# Mezz_connector.net
KiCad netlist of a schematic drawn in Altium Designer
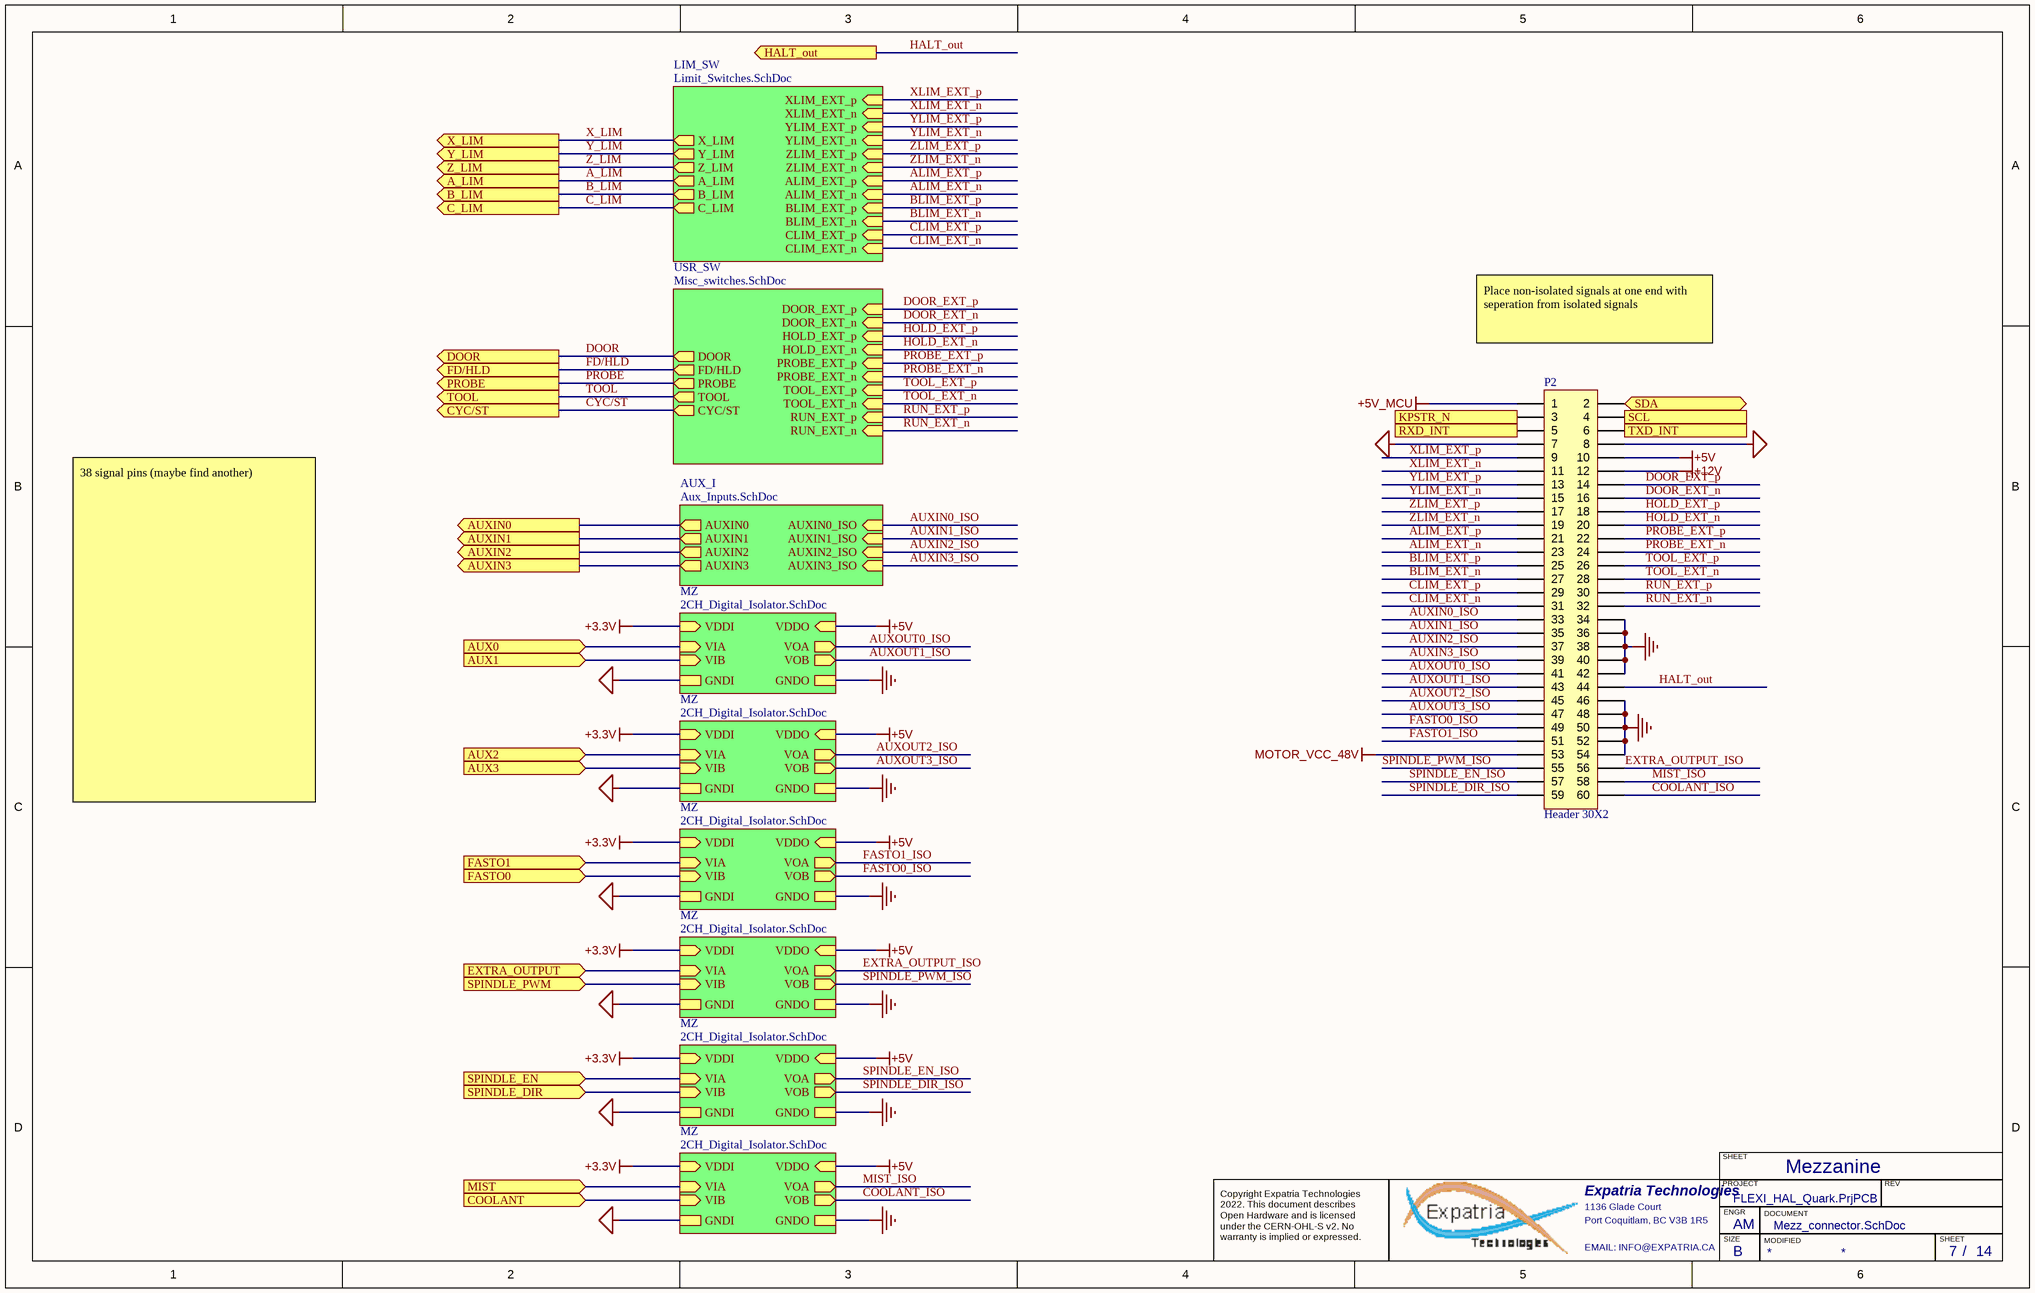
[diagram p0: Mezz_connector.SchDoc]

(export (version "E")
  (design (tool "Eeschema 10.0.6"))
  (components
    (comp (ref "P2")
      (value "Header 30X2")
      (footprint "Flexi-Quark-Mezzanine")
      (description "Header, 30-Pin, Dual row")
      (fields (field (name "PUBLISHER") "Altium Limited"))
      (libsource (lib "Miscellaneous Connectors") (part "Header 30X2"))
    )
  )
  (nets
    (net (code "2") (name "+5V") (class "Default")
      (node (ref "P2") (pin "10") (pinfunction "10_10") (pintype "passive"))
    )
    (net (code "3") (name "+5V_MCU") (class "Default")
      (node (ref "P2") (pin "1") (pinfunction "1_1") (pintype "passive"))
    )
    (net (code "4") (name "+12V") (class "Default")
      (node (ref "P2") (pin "12") (pinfunction "12_12") (pintype "passive"))
    )
    (net (code "5") (name "/ALIM_EXT_n") (class "Default")
      (node (ref "P2") (pin "23") (pinfunction "23_23") (pintype "passive"))
    )
    (net (code "6") (name "/ALIM_EXT_p") (class "Default")
      (node (ref "P2") (pin "21") (pinfunction "21_21") (pintype "passive"))
    )
    (net (code "12") (name "/AUXIN0_ISO") (class "Default")
      (node (ref "P2") (pin "33") (pinfunction "33_33") (pintype "passive"))
    )
    (net (code "14") (name "/AUXIN1_ISO") (class "Default")
      (node (ref "P2") (pin "35") (pinfunction "35_35") (pintype "passive"))
    )
    (net (code "16") (name "/AUXIN2_ISO") (class "Default")
      (node (ref "P2") (pin "37") (pinfunction "37_37") (pintype "passive"))
    )
    (net (code "18") (name "/AUXIN3_ISO") (class "Default")
      (node (ref "P2") (pin "39") (pinfunction "39_39") (pintype "passive"))
    )
    (net (code "19") (name "/AUXOUT0_ISO") (class "Default")
      (node (ref "P2") (pin "41") (pinfunction "41_41") (pintype "passive"))
    )
    (net (code "20") (name "/AUXOUT1_ISO") (class "Default")
      (node (ref "P2") (pin "43") (pinfunction "43_43") (pintype "passive"))
    )
    (net (code "21") (name "/AUXOUT2_ISO") (class "Default")
      (node (ref "P2") (pin "45") (pinfunction "45_45") (pintype "passive"))
    )
    (net (code "22") (name "/AUXOUT3_ISO") (class "Default")
      (node (ref "P2") (pin "47") (pinfunction "47_47") (pintype "passive"))
    )
    (net (code "24") (name "/BLIM_EXT_n") (class "Default")
      (node (ref "P2") (pin "27") (pinfunction "27_27") (pintype "passive"))
    )
    (net (code "25") (name "/BLIM_EXT_p") (class "Default")
      (node (ref "P2") (pin "25") (pinfunction "25_25") (pintype "passive"))
    )
    (net (code "27") (name "/CLIM_EXT_n") (class "Default")
      (node (ref "P2") (pin "31") (pinfunction "31_31") (pintype "passive"))
    )
    (net (code "28") (name "/CLIM_EXT_p") (class "Default")
      (node (ref "P2") (pin "29") (pinfunction "29_29") (pintype "passive"))
    )
    (net (code "30") (name "/COOLANT_ISO") (class "Default")
      (node (ref "P2") (pin "60") (pinfunction "60_60") (pintype "passive"))
    )
    (net (code "34") (name "/DOOR_EXT_n") (class "Default")
      (node (ref "P2") (pin "16") (pinfunction "16_16") (pintype "passive"))
    )
    (net (code "35") (name "/DOOR_EXT_p") (class "Default")
      (node (ref "P2") (pin "14") (pinfunction "14_14") (pintype "passive"))
    )
    (net (code "37") (name "/EXTRA_OUTPUT_ISO") (class "Default")
      (node (ref "P2") (pin "56") (pinfunction "56_56") (pintype "passive"))
    )
    (net (code "39") (name "/FASTO0_ISO") (class "Default")
      (node (ref "P2") (pin "49") (pinfunction "49_49") (pintype "passive"))
    )
    (net (code "41") (name "/FASTO1_ISO") (class "Default")
      (node (ref "P2") (pin "51") (pinfunction "51_51") (pintype "passive"))
    )
    (net (code "43") (name "/HALT_out") (class "Default")
      (node (ref "P2") (pin "44") (pinfunction "44_44") (pintype "passive"))
    )
    (net (code "44") (name "/HOLD_EXT_n") (class "Default")
      (node (ref "P2") (pin "20") (pinfunction "20_20") (pintype "passive"))
    )
    (net (code "45") (name "/HOLD_EXT_p") (class "Default")
      (node (ref "P2") (pin "18") (pinfunction "18_18") (pintype "passive"))
    )
    (net (code "46") (name "/KPSTR_N") (class "Default")
      (node (ref "P2") (pin "3") (pinfunction "3_3") (pintype "passive"))
    )
    (net (code "48") (name "/MIST_ISO") (class "Default")
      (node (ref "P2") (pin "58") (pinfunction "58_58") (pintype "passive"))
    )
    (net (code "50") (name "/PROBE_EXT_n") (class "Default")
      (node (ref "P2") (pin "24") (pinfunction "24_24") (pintype "passive"))
    )
    (net (code "51") (name "/PROBE_EXT_p") (class "Default")
      (node (ref "P2") (pin "22") (pinfunction "22_22") (pintype "passive"))
    )
    (net (code "52") (name "/RUN_EXT_n") (class "Default")
      (node (ref "P2") (pin "32") (pinfunction "32_32") (pintype "passive"))
    )
    (net (code "53") (name "/RUN_EXT_p") (class "Default")
      (node (ref "P2") (pin "30") (pinfunction "30_30") (pintype "passive"))
    )
    (net (code "54") (name "/RXD_INT") (class "Default")
      (node (ref "P2") (pin "5") (pinfunction "5_5") (pintype "passive"))
    )
    (net (code "55") (name "/SCL") (class "Default")
      (node (ref "P2") (pin "4") (pinfunction "4_4") (pintype "passive"))
    )
    (net (code "56") (name "/SDA") (class "Default")
      (node (ref "P2") (pin "2") (pinfunction "2_2") (pintype "passive"))
    )
    (net (code "58") (name "/SPINDLE_DIR_ISO") (class "Default")
      (node (ref "P2") (pin "59") (pinfunction "59_59") (pintype "passive"))
    )
    (net (code "60") (name "/SPINDLE_EN_ISO") (class "Default")
      (node (ref "P2") (pin "57") (pinfunction "57_57") (pintype "passive"))
    )
    (net (code "62") (name "/SPINDLE_PWM_ISO") (class "Default")
      (node (ref "P2") (pin "55") (pinfunction "55_55") (pintype "passive"))
    )
    (net (code "64") (name "/TOOL_EXT_n") (class "Default")
      (node (ref "P2") (pin "28") (pinfunction "28_28") (pintype "passive"))
    )
    (net (code "65") (name "/TOOL_EXT_p") (class "Default")
      (node (ref "P2") (pin "26") (pinfunction "26_26") (pintype "passive"))
    )
    (net (code "66") (name "/TXD_INT") (class "Default")
      (node (ref "P2") (pin "6") (pinfunction "6_6") (pintype "passive"))
    )
    (net (code "67") (name "/XLIM_EXT_n") (class "Default")
      (node (ref "P2") (pin "11") (pinfunction "11_11") (pintype "passive"))
    )
    (net (code "68") (name "/XLIM_EXT_p") (class "Default")
      (node (ref "P2") (pin "9") (pinfunction "9_9") (pintype "passive"))
    )
    (net (code "70") (name "/YLIM_EXT_n") (class "Default")
      (node (ref "P2") (pin "15") (pinfunction "15_15") (pintype "passive"))
    )
    (net (code "71") (name "/YLIM_EXT_p") (class "Default")
      (node (ref "P2") (pin "13") (pinfunction "13_13") (pintype "passive"))
    )
    (net (code "73") (name "/ZLIM_EXT_n") (class "Default")
      (node (ref "P2") (pin "19") (pinfunction "19_19") (pintype "passive"))
    )
    (net (code "74") (name "/ZLIM_EXT_p") (class "Default")
      (node (ref "P2") (pin "17") (pinfunction "17_17") (pintype "passive"))
    )
    (net (code "76") (name "GND") (class "Default")
      (node (ref "P2") (pin "34") (pinfunction "34_34") (pintype "passive"))
      (node (ref "P2") (pin "36") (pinfunction "36_36") (pintype "passive"))
      (node (ref "P2") (pin "38") (pinfunction "38_38") (pintype "passive"))
      (node (ref "P2") (pin "40") (pinfunction "40_40") (pintype "passive"))
      (node (ref "P2") (pin "42") (pinfunction "42_42") (pintype "passive"))
      (node (ref "P2") (pin "46") (pinfunction "46_46") (pintype "passive"))
      (node (ref "P2") (pin "48") (pinfunction "48_48") (pintype "passive"))
      (node (ref "P2") (pin "50") (pinfunction "50_50") (pintype "passive"))
      (node (ref "P2") (pin "52") (pinfunction "52_52") (pintype "passive"))
      (node (ref "P2") (pin "54") (pinfunction "54_54") (pintype "passive"))
    )
    (net (code "77") (name "MCU_GND") (class "Default")
      (node (ref "P2") (pin "7") (pinfunction "7_7") (pintype "passive"))
      (node (ref "P2") (pin "8") (pinfunction "8_8") (pintype "passive"))
    )
    (net (code "78") (name "MOTOR_VCC_48V") (class "Default")
      (node (ref "P2") (pin "53") (pinfunction "53_53") (pintype "passive"))
    )
  )
)
